# ESP8266_CLOCK.net
KiCad netlist of a schematic drawn in Altium Designer
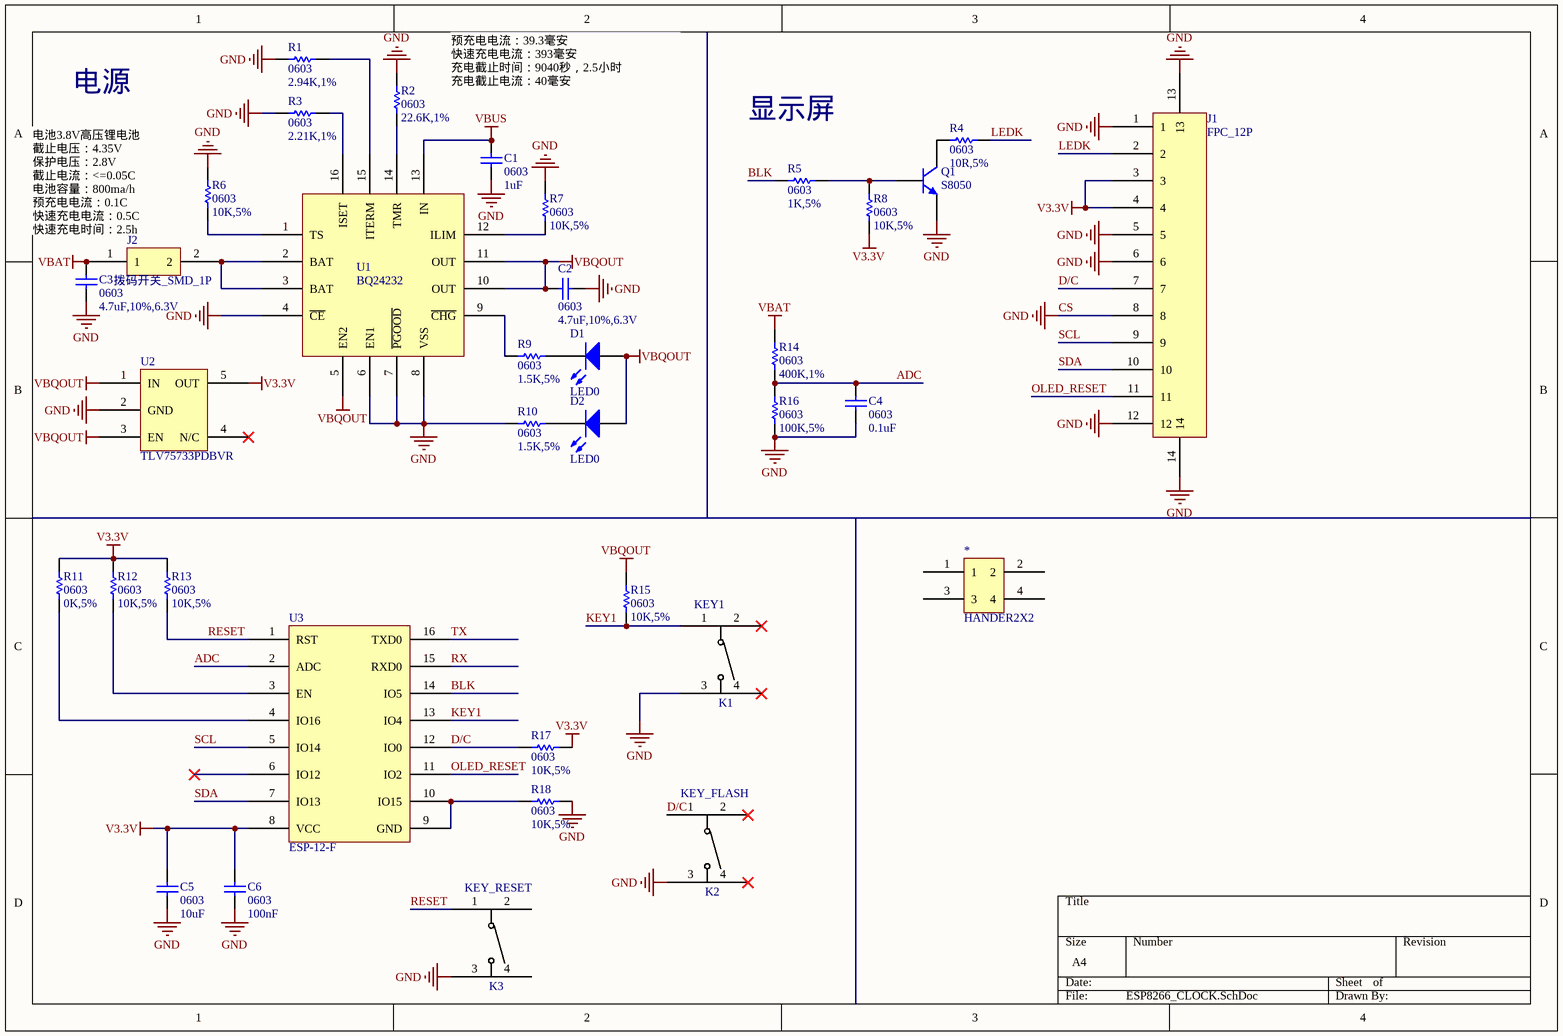
[diagram p0: ESP8266_CLOCK.SchDoc]

(export (version "E")
  (design (tool "Eeschema 10.0.6"))
  (components
    (comp (ref "*")
      (value "HANDER2X2")
      (description "2*2排母弯插")
      (libsource (lib "ESP8266_COLOCK") (part "HANDER2X2"))
    )
    (comp (ref "C1")
      (value "0603")
      (footprint "RAD-0.3")
      (description "Capacitor")
      (fields (field (name "ALTIUM_VALUE") "1uF") (field (name "PUBLISHER") "Altium Limited"))
      (libsource (lib "Miscellaneous Devices") (part "Cap"))
    )
    (comp (ref "C2")
      (value "0603")
      (footprint "RAD-0.3")
      (description "Capacitor")
      (fields (field (name "ALTIUM_VALUE") "4.7uF,10%,6.3V") (field (name "PUBLISHER") "Altium Limited"))
      (libsource (lib "Miscellaneous Devices") (part "Cap"))
    )
    (comp (ref "C3")
      (value "0603")
      (footprint "RAD-0.3")
      (description "Capacitor")
      (fields (field (name "ALTIUM_VALUE") "4.7uF,10%,6.3V") (field (name "PUBLISHER") "Altium Limited"))
      (libsource (lib "Miscellaneous Devices") (part "Cap"))
    )
    (comp (ref "C4")
      (value "0603")
      (footprint "RAD-0.3")
      (description "Capacitor")
      (fields (field (name "ALTIUM_VALUE") "0.1uF") (field (name "PUBLISHER") "Altium Limited"))
      (libsource (lib "Miscellaneous Devices") (part "Cap"))
    )
    (comp (ref "C5")
      (value "0603")
      (footprint "RAD-0.3")
      (description "Capacitor")
      (fields (field (name "ALTIUM_VALUE") "10uF") (field (name "PUBLISHER") "Altium Limited"))
      (libsource (lib "Miscellaneous Devices") (part "Cap"))
    )
    (comp (ref "C6")
      (value "0603")
      (footprint "RAD-0.3")
      (description "Capacitor")
      (fields (field (name "ALTIUM_VALUE") "100nF") (field (name "PUBLISHER") "Altium Limited"))
      (libsource (lib "Miscellaneous Devices") (part "Cap"))
    )
    (comp (ref "D1")
      (value "LED0")
      (footprint "LED-0")
      (description "Typical INFRARED GaAs LED")
      (fields (field (name "PUBLISHER") "Altium Limited"))
      (libsource (lib "Miscellaneous Devices") (part "LED0"))
    )
    (comp (ref "D2")
      (value "LED0")
      (footprint "LED-0")
      (description "Typical INFRARED GaAs LED")
      (fields (field (name "PUBLISHER") "Altium Limited"))
      (libsource (lib "Miscellaneous Devices") (part "LED0"))
    )
    (comp (ref "J1")
      (value "FPC_12P")
      (description "FPC 0.5mm间距 12P 下接式")
      (libsource (lib "ESP8266_COLOCK") (part "FPC_12P"))
    )
    (comp (ref "J2") (value "拨码开关_SMD_1P") (libsource (lib "ESP8266_COLOCK") (part "拨码开关_SMD_1P")))
    (comp (ref "K1") (value "KEY1") (description "乌龟按键") (libsource (lib "ESP8266_COLOCK") (part "KEY_4PIN")))
    (comp (ref "K2")
      (value "KEY_FLASH")
      (description "乌龟按键")
      (libsource (lib "ESP8266_COLOCK") (part "KEY_4PIN"))
    )
    (comp (ref "K3")
      (value "KEY_RESET")
      (description "乌龟按键")
      (libsource (lib "ESP8266_COLOCK") (part "KEY_4PIN"))
    )
    (comp (ref "Q1")
      (value "S8050")
      (footprint "TO-226-AA")
      (description "NPN Bipolar Transistor")
      (fields (field (name "PUBLISHER") "Altium Limited"))
      (libsource (lib "Miscellaneous Devices") (part "NPN"))
    )
    (comp (ref "R1")
      (value "0603")
      (footprint "AXIAL-0.3")
      (description "Resistor")
      (fields (field (name "ALTIUM_VALUE") "2.94K,1%") (field (name "PUBLISHER") "Altium Limited"))
      (libsource (lib "Miscellaneous Devices") (part "Res1"))
    )
    (comp (ref "R2")
      (value "0603")
      (footprint "AXIAL-0.3")
      (description "Resistor")
      (fields (field (name "ALTIUM_VALUE") "22.6K,1%") (field (name "PUBLISHER") "Altium Limited"))
      (libsource (lib "Miscellaneous Devices") (part "Res1"))
    )
    (comp (ref "R3")
      (value "0603")
      (footprint "AXIAL-0.3")
      (description "Resistor")
      (fields (field (name "ALTIUM_VALUE") "2.21K,1%") (field (name "PUBLISHER") "Altium Limited"))
      (libsource (lib "Miscellaneous Devices") (part "Res1"))
    )
    (comp (ref "R4")
      (value "0603")
      (footprint "AXIAL-0.3")
      (description "Resistor")
      (fields (field (name "ALTIUM_VALUE") "10R,5%") (field (name "PUBLISHER") "Altium Limited"))
      (libsource (lib "Miscellaneous Devices") (part "Res1"))
    )
    (comp (ref "R5")
      (value "0603")
      (footprint "AXIAL-0.3")
      (description "Resistor")
      (fields (field (name "ALTIUM_VALUE") "1K,5%") (field (name "PUBLISHER") "Altium Limited"))
      (libsource (lib "Miscellaneous Devices") (part "Res1"))
    )
    (comp (ref "R6")
      (value "0603")
      (footprint "AXIAL-0.3")
      (description "Resistor")
      (fields (field (name "ALTIUM_VALUE") "10K,5%") (field (name "PUBLISHER") "Altium Limited"))
      (libsource (lib "Miscellaneous Devices") (part "Res1"))
    )
    (comp (ref "R7")
      (value "0603")
      (footprint "AXIAL-0.3")
      (description "Resistor")
      (fields (field (name "ALTIUM_VALUE") "10K,5%") (field (name "PUBLISHER") "Altium Limited"))
      (libsource (lib "Miscellaneous Devices") (part "Res1"))
    )
    (comp (ref "R8")
      (value "0603")
      (footprint "AXIAL-0.3")
      (description "Resistor")
      (fields (field (name "ALTIUM_VALUE") "10K,5%") (field (name "PUBLISHER") "Altium Limited"))
      (libsource (lib "Miscellaneous Devices") (part "Res1"))
    )
    (comp (ref "R9")
      (value "0603")
      (footprint "AXIAL-0.3")
      (description "Resistor")
      (fields (field (name "ALTIUM_VALUE") "1.5K,5%") (field (name "PUBLISHER") "Altium Limited"))
      (libsource (lib "Miscellaneous Devices") (part "Res1"))
    )
    (comp (ref "R10")
      (value "0603")
      (footprint "AXIAL-0.3")
      (description "Resistor")
      (fields (field (name "ALTIUM_VALUE") "1.5K,5%") (field (name "PUBLISHER") "Altium Limited"))
      (libsource (lib "Miscellaneous Devices") (part "Res1"))
    )
    (comp (ref "R11")
      (value "0603")
      (footprint "AXIAL-0.3")
      (description "Resistor")
      (fields (field (name "ALTIUM_VALUE") "0K,5%") (field (name "PUBLISHER") "Altium Limited"))
      (libsource (lib "Miscellaneous Devices") (part "Res1"))
    )
    (comp (ref "R12")
      (value "0603")
      (footprint "AXIAL-0.3")
      (description "Resistor")
      (fields (field (name "ALTIUM_VALUE") "10K,5%") (field (name "PUBLISHER") "Altium Limited"))
      (libsource (lib "Miscellaneous Devices") (part "Res1"))
    )
    (comp (ref "R13")
      (value "0603")
      (footprint "AXIAL-0.3")
      (description "Resistor")
      (fields (field (name "ALTIUM_VALUE") "10K,5%") (field (name "PUBLISHER") "Altium Limited"))
      (libsource (lib "Miscellaneous Devices") (part "Res1"))
    )
    (comp (ref "R14")
      (value "0603")
      (footprint "AXIAL-0.3")
      (description "Resistor")
      (fields (field (name "ALTIUM_VALUE") "400K,1%") (field (name "PUBLISHER") "Altium Limited"))
      (libsource (lib "Miscellaneous Devices") (part "Res1"))
    )
    (comp (ref "R15")
      (value "0603")
      (footprint "AXIAL-0.3")
      (description "Resistor")
      (fields (field (name "ALTIUM_VALUE") "10K,5%") (field (name "PUBLISHER") "Altium Limited"))
      (libsource (lib "Miscellaneous Devices") (part "Res1"))
    )
    (comp (ref "R16")
      (value "0603")
      (footprint "AXIAL-0.3")
      (description "Resistor")
      (fields (field (name "ALTIUM_VALUE") "100K,5%") (field (name "PUBLISHER") "Altium Limited"))
      (libsource (lib "Miscellaneous Devices") (part "Res1"))
    )
    (comp (ref "R17")
      (value "0603")
      (footprint "AXIAL-0.3")
      (description "Resistor")
      (fields (field (name "ALTIUM_VALUE") "10K,5%") (field (name "PUBLISHER") "Altium Limited"))
      (libsource (lib "Miscellaneous Devices") (part "Res1"))
    )
    (comp (ref "R18")
      (value "0603")
      (footprint "AXIAL-0.3")
      (description "Resistor")
      (fields (field (name "ALTIUM_VALUE") "10K,5%") (field (name "PUBLISHER") "Altium Limited"))
      (libsource (lib "Miscellaneous Devices") (part "Res1"))
    )
    (comp (ref "U1")
      (value "BQ24232")
      (footprint "BQ24232")
      (description "电池管理芯片")
      (libsource (lib "ESP8266_COLOCK") (part "BQ24232"))
    )
    (comp (ref "U2")
      (value "TLV75733PDBVR")
      (description "低压差稳压芯片，1A")
      (libsource (lib "ESP8266_COLOCK") (part "TLV75733PDBVR"))
    )
    (comp (ref "U3")
      (value "ESP-12-F")
      (description "安信可ESP8266模组")
      (libsource (lib "ESP8266_COLOCK") (part "ESP-12-F"))
    )
  )
  (nets
    (net (code "1") (name "/ADC") (class "Default")
      (node (ref "C4") (pin "2") (pinfunction "2_2") (pintype "passive"))
      (node (ref "R14") (pin "2") (pinfunction "2_2") (pintype "passive"))
      (node (ref "R16") (pin "1") (pinfunction "1_1") (pintype "passive"))
      (node (ref "U3") (pin "2") (pinfunction "ADC_2") (pintype "passive"))
    )
    (net (code "2") (name "/BLK") (class "Default")
      (node (ref "R5") (pin "2") (pinfunction "2_2") (pintype "passive"))
      (node (ref "U3") (pin "14") (pinfunction "IO5_14") (pintype "passive"))
    )
    (net (code "3") (name "/D{slash}C") (class "Default")
      (node (ref "J1") (pin "7") (pinfunction "7_7") (pintype "passive"))
      (node (ref "K2") (pin "1") (pinfunction "1_1") (pintype "passive"))
      (node (ref "R17") (pin "2") (pinfunction "2_2") (pintype "passive"))
      (node (ref "U3") (pin "12") (pinfunction "IO0_12") (pintype "passive"))
    )
    (net (code "4") (name "/KEY1") (class "Default")
      (node (ref "K1") (pin "1") (pinfunction "1_1") (pintype "passive"))
      (node (ref "R15") (pin "2") (pinfunction "2_2") (pintype "passive"))
      (node (ref "U3") (pin "13") (pinfunction "IO4_13") (pintype "passive"))
    )
    (net (code "5") (name "/LEDK") (class "Default")
      (node (ref "J1") (pin "2") (pinfunction "2_2") (pintype "passive"))
      (node (ref "R4") (pin "1") (pinfunction "1_1") (pintype "passive"))
    )
    (net (code "6") (name "/OLED_RESET") (class "Default")
      (node (ref "J1") (pin "11") (pinfunction "11_11") (pintype "passive"))
      (node (ref "U3") (pin "11") (pinfunction "IO2_11") (pintype "passive"))
    )
    (net (code "7") (name "/RESET") (class "Default")
      (node (ref "K3") (pin "1") (pinfunction "1_1") (pintype "passive"))
      (node (ref "R13") (pin "1") (pinfunction "1_1") (pintype "passive"))
      (node (ref "U3") (pin "1") (pinfunction "RST_1") (pintype "passive"))
    )
    (net (code "8") (name "/RX") (class "Default")
      (node (ref "U3") (pin "15") (pinfunction "RXD0_15") (pintype "passive"))
    )
    (net (code "9") (name "/SCL") (class "Default")
      (node (ref "J1") (pin "9") (pinfunction "9_9") (pintype "passive"))
      (node (ref "U3") (pin "5") (pinfunction "IO14_5") (pintype "passive"))
    )
    (net (code "10") (name "/SDA") (class "Default")
      (node (ref "J1") (pin "10") (pinfunction "10_10") (pintype "passive"))
      (node (ref "U3") (pin "7") (pinfunction "IO13_7") (pintype "passive"))
    )
    (net (code "11") (name "/TX") (class "Default")
      (node (ref "U3") (pin "16") (pinfunction "TXD0_16") (pintype "passive"))
    )
    (net (code "12") (name "GND") (class "Default")
      (node (ref "C1") (pin "1") (pinfunction "1_1") (pintype "passive"))
      (node (ref "C2") (pin "1") (pinfunction "1_1") (pintype "passive"))
      (node (ref "C3") (pin "2") (pinfunction "2_2") (pintype "passive"))
      (node (ref "C4") (pin "1") (pinfunction "1_1") (pintype "passive"))
      (node (ref "C5") (pin "1") (pinfunction "1_1") (pintype "passive"))
      (node (ref "C6") (pin "1") (pinfunction "1_1") (pintype "passive"))
      (node (ref "J1") (pin "1") (pinfunction "1_1") (pintype "passive"))
      (node (ref "J1") (pin "12") (pinfunction "12_12") (pintype "passive"))
      (node (ref "J1") (pin "13") (pinfunction "13_13") (pintype "passive"))
      (node (ref "J1") (pin "14") (pinfunction "14_14") (pintype "passive"))
      (node (ref "J1") (pin "5") (pinfunction "5_5") (pintype "passive"))
      (node (ref "J1") (pin "6") (pinfunction "6_6") (pintype "passive"))
      (node (ref "J1") (pin "8") (pinfunction "8_8") (pintype "passive"))
      (node (ref "K1") (pin "3") (pinfunction "3_3") (pintype "passive"))
      (node (ref "K2") (pin "3") (pinfunction "3_3") (pintype "passive"))
      (node (ref "K3") (pin "3") (pinfunction "3_3") (pintype "passive"))
      (node (ref "Q1") (pin "3") (pinfunction "E_3") (pintype "passive"))
      (node (ref "R1") (pin "2") (pinfunction "2_2") (pintype "passive"))
      (node (ref "R10") (pin "2") (pinfunction "2_2") (pintype "passive"))
      (node (ref "R16") (pin "2") (pinfunction "2_2") (pintype "passive"))
      (node (ref "R18") (pin "1") (pinfunction "1_1") (pintype "passive"))
      (node (ref "R2") (pin "2") (pinfunction "2_2") (pintype "passive"))
      (node (ref "R3") (pin "2") (pinfunction "2_2") (pintype "passive"))
      (node (ref "R6") (pin "1") (pinfunction "1_1") (pintype "passive"))
      (node (ref "R7") (pin "2") (pinfunction "2_2") (pintype "passive"))
      (node (ref "U1") (pin "4") (pinfunction "~{CE}_4") (pintype "passive"))
      (node (ref "U1") (pin "6") (pinfunction "EN1_6") (pintype "passive"))
      (node (ref "U1") (pin "7") (pinfunction "~{PGOOD}_7") (pintype "passive"))
      (node (ref "U1") (pin "8") (pinfunction "VSS_8") (pintype "passive"))
      (node (ref "U2") (pin "2") (pinfunction "GND_2") (pintype "passive"))
    )
    (net (code "13") (name "Net-(D1-K)") (class "Default")
      (node (ref "D1") (pin "2") (pinfunction "K_2") (pintype "passive"))
      (node (ref "R9") (pin "1") (pinfunction "1_1") (pintype "passive"))
    )
    (net (code "14") (name "Net-(D2-K)") (class "Default")
      (node (ref "D2") (pin "2") (pinfunction "K_2") (pintype "passive"))
      (node (ref "R10") (pin "1") (pinfunction "1_1") (pintype "passive"))
    )
    (net (code "15") (name "Net-(J2-Pad2)") (class "Default")
      (node (ref "J2") (pin "2") (pinfunction "2_2") (pintype "passive"))
      (node (ref "U1") (pin "2") (pinfunction "BAT_2") (pintype "passive"))
      (node (ref "U1") (pin "3") (pinfunction "BAT_3") (pintype "passive"))
    )
    (net (code "16") (name "Net-(Q1-B)") (class "Default")
      (node (ref "Q1") (pin "2") (pinfunction "B_2") (pintype "passive"))
      (node (ref "R5") (pin "1") (pinfunction "1_1") (pintype "passive"))
      (node (ref "R8") (pin "2") (pinfunction "2_2") (pintype "passive"))
    )
    (net (code "17") (name "Net-(Q1-C)") (class "Default")
      (node (ref "Q1") (pin "1") (pinfunction "C_1") (pintype "passive"))
      (node (ref "R4") (pin "2") (pinfunction "2_2") (pintype "passive"))
    )
    (net (code "18") (name "Net-(U1-ILIM)") (class "Default")
      (node (ref "R7") (pin "1") (pinfunction "1_1") (pintype "passive"))
      (node (ref "U1") (pin "12") (pinfunction "ILIM_12") (pintype "passive"))
    )
    (net (code "19") (name "Net-(U1-ISET)") (class "Default")
      (node (ref "R3") (pin "1") (pinfunction "1_1") (pintype "passive"))
      (node (ref "U1") (pin "16") (pinfunction "ISET_16") (pintype "passive"))
    )
    (net (code "20") (name "Net-(U1-ITERM)") (class "Default")
      (node (ref "R1") (pin "1") (pinfunction "1_1") (pintype "passive"))
      (node (ref "U1") (pin "15") (pinfunction "ITERM_15") (pintype "passive"))
    )
    (net (code "21") (name "Net-(U1-TMR)") (class "Default")
      (node (ref "R2") (pin "1") (pinfunction "1_1") (pintype "passive"))
      (node (ref "U1") (pin "14") (pinfunction "TMR_14") (pintype "passive"))
    )
    (net (code "22") (name "Net-(U1-TS)") (class "Default")
      (node (ref "R6") (pin "2") (pinfunction "2_2") (pintype "passive"))
      (node (ref "U1") (pin "1") (pinfunction "TS_1") (pintype "passive"))
    )
    (net (code "23") (name "Net-(U1-~{CHG})") (class "Default")
      (node (ref "R9") (pin "2") (pinfunction "2_2") (pintype "passive"))
      (node (ref "U1") (pin "9") (pinfunction "~{CHG}_9") (pintype "passive"))
    )
    (net (code "24") (name "Net-(U3-EN)") (class "Default")
      (node (ref "R12") (pin "2") (pinfunction "2_2") (pintype "passive"))
      (node (ref "U3") (pin "3") (pinfunction "EN_3") (pintype "passive"))
    )
    (net (code "25") (name "Net-(U3-GND)") (class "Default")
      (node (ref "R18") (pin "2") (pinfunction "2_2") (pintype "passive"))
      (node (ref "U3") (pin "10") (pinfunction "IO15_10") (pintype "passive"))
      (node (ref "U3") (pin "9") (pinfunction "GND_9") (pintype "passive"))
    )
    (net (code "26") (name "Net-(U3-IO16)") (class "Default")
      (node (ref "R11") (pin "1") (pinfunction "1_1") (pintype "passive"))
      (node (ref "U3") (pin "4") (pinfunction "IO16_4") (pintype "passive"))
    )
    (net (code "27") (name "V3.3V") (class "Default")
      (node (ref "C5") (pin "2") (pinfunction "2_2") (pintype "passive"))
      (node (ref "C6") (pin "2") (pinfunction "2_2") (pintype "passive"))
      (node (ref "J1") (pin "3") (pinfunction "3_3") (pintype "passive"))
      (node (ref "J1") (pin "4") (pinfunction "4_4") (pintype "passive"))
      (node (ref "R11") (pin "2") (pinfunction "2_2") (pintype "passive"))
      (node (ref "R12") (pin "1") (pinfunction "1_1") (pintype "passive"))
      (node (ref "R13") (pin "2") (pinfunction "2_2") (pintype "passive"))
      (node (ref "R17") (pin "1") (pinfunction "1_1") (pintype "passive"))
      (node (ref "R8") (pin "1") (pinfunction "1_1") (pintype "passive"))
      (node (ref "U2") (pin "5") (pinfunction "OUT_5") (pintype "passive"))
      (node (ref "U3") (pin "8") (pinfunction "VCC_8") (pintype "passive"))
    )
    (net (code "28") (name "VBAT") (class "Default")
      (node (ref "C3") (pin "1") (pinfunction "1_1") (pintype "passive"))
      (node (ref "J2") (pin "1") (pinfunction "1_1") (pintype "passive"))
      (node (ref "R14") (pin "1") (pinfunction "1_1") (pintype "passive"))
    )
    (net (code "29") (name "VBQOUT") (class "Default")
      (node (ref "C2") (pin "2") (pinfunction "2_2") (pintype "passive"))
      (node (ref "D1") (pin "1") (pinfunction "A_1") (pintype "passive"))
      (node (ref "D2") (pin "1") (pinfunction "A_1") (pintype "passive"))
      (node (ref "R15") (pin "1") (pinfunction "1_1") (pintype "passive"))
      (node (ref "U1") (pin "10") (pinfunction "OUT_10") (pintype "passive"))
      (node (ref "U1") (pin "11") (pinfunction "OUT_11") (pintype "passive"))
      (node (ref "U1") (pin "5") (pinfunction "EN2_5") (pintype "passive"))
      (node (ref "U2") (pin "1") (pinfunction "IN_1") (pintype "passive"))
      (node (ref "U2") (pin "3") (pinfunction "EN_3") (pintype "passive"))
    )
    (net (code "30") (name "VBUS") (class "Default")
      (node (ref "C1") (pin "2") (pinfunction "2_2") (pintype "passive"))
      (node (ref "U1") (pin "13") (pinfunction "IN_13") (pintype "passive"))
    )
    (net (code "31") (name "unconnected-(*-Pad1)") (class "Default")
      (node (ref "*") (pin "1") (pinfunction "1_1") (pintype "passive"))
    )
    (net (code "32") (name "unconnected-(*-Pad2)") (class "Default")
      (node (ref "*") (pin "2") (pinfunction "2_2") (pintype "passive"))
    )
    (net (code "33") (name "unconnected-(*-Pad3)") (class "Default")
      (node (ref "*") (pin "3") (pinfunction "3_3") (pintype "passive"))
    )
    (net (code "34") (name "unconnected-(*-Pad4)") (class "Default")
      (node (ref "*") (pin "4") (pinfunction "4_4") (pintype "passive"))
    )
    (net (code "35") (name "unconnected-(K1-Pad2)") (class "Default")
      (node (ref "K1") (pin "2") (pinfunction "2_2") (pintype "passive+no_connect"))
    )
    (net (code "36") (name "unconnected-(K1-Pad4)") (class "Default")
      (node (ref "K1") (pin "4") (pinfunction "4_4") (pintype "passive+no_connect"))
    )
    (net (code "37") (name "unconnected-(K2-Pad2)") (class "Default")
      (node (ref "K2") (pin "2") (pinfunction "2_2") (pintype "passive+no_connect"))
    )
    (net (code "38") (name "unconnected-(K2-Pad4)") (class "Default")
      (node (ref "K2") (pin "4") (pinfunction "4_4") (pintype "passive+no_connect"))
    )
    (net (code "39") (name "unconnected-(K3-Pad2)") (class "Default")
      (node (ref "K3") (pin "2") (pinfunction "2_2") (pintype "passive"))
    )
    (net (code "40") (name "unconnected-(K3-Pad4)") (class "Default")
      (node (ref "K3") (pin "4") (pinfunction "4_4") (pintype "passive"))
    )
    (net (code "41") (name "unconnected-(U2-N{slash}C-Pad4)") (class "Default")
      (node (ref "U2") (pin "4") (pinfunction "N/C_4") (pintype "passive+no_connect"))
    )
    (net (code "42") (name "unconnected-(U3-IO12-Pad6)") (class "Default")
      (node (ref "U3") (pin "6") (pinfunction "IO12_6") (pintype "passive+no_connect"))
    )
  )
)
